# schematic.net
KiCad netlist of a schematic drawn in EAGLE
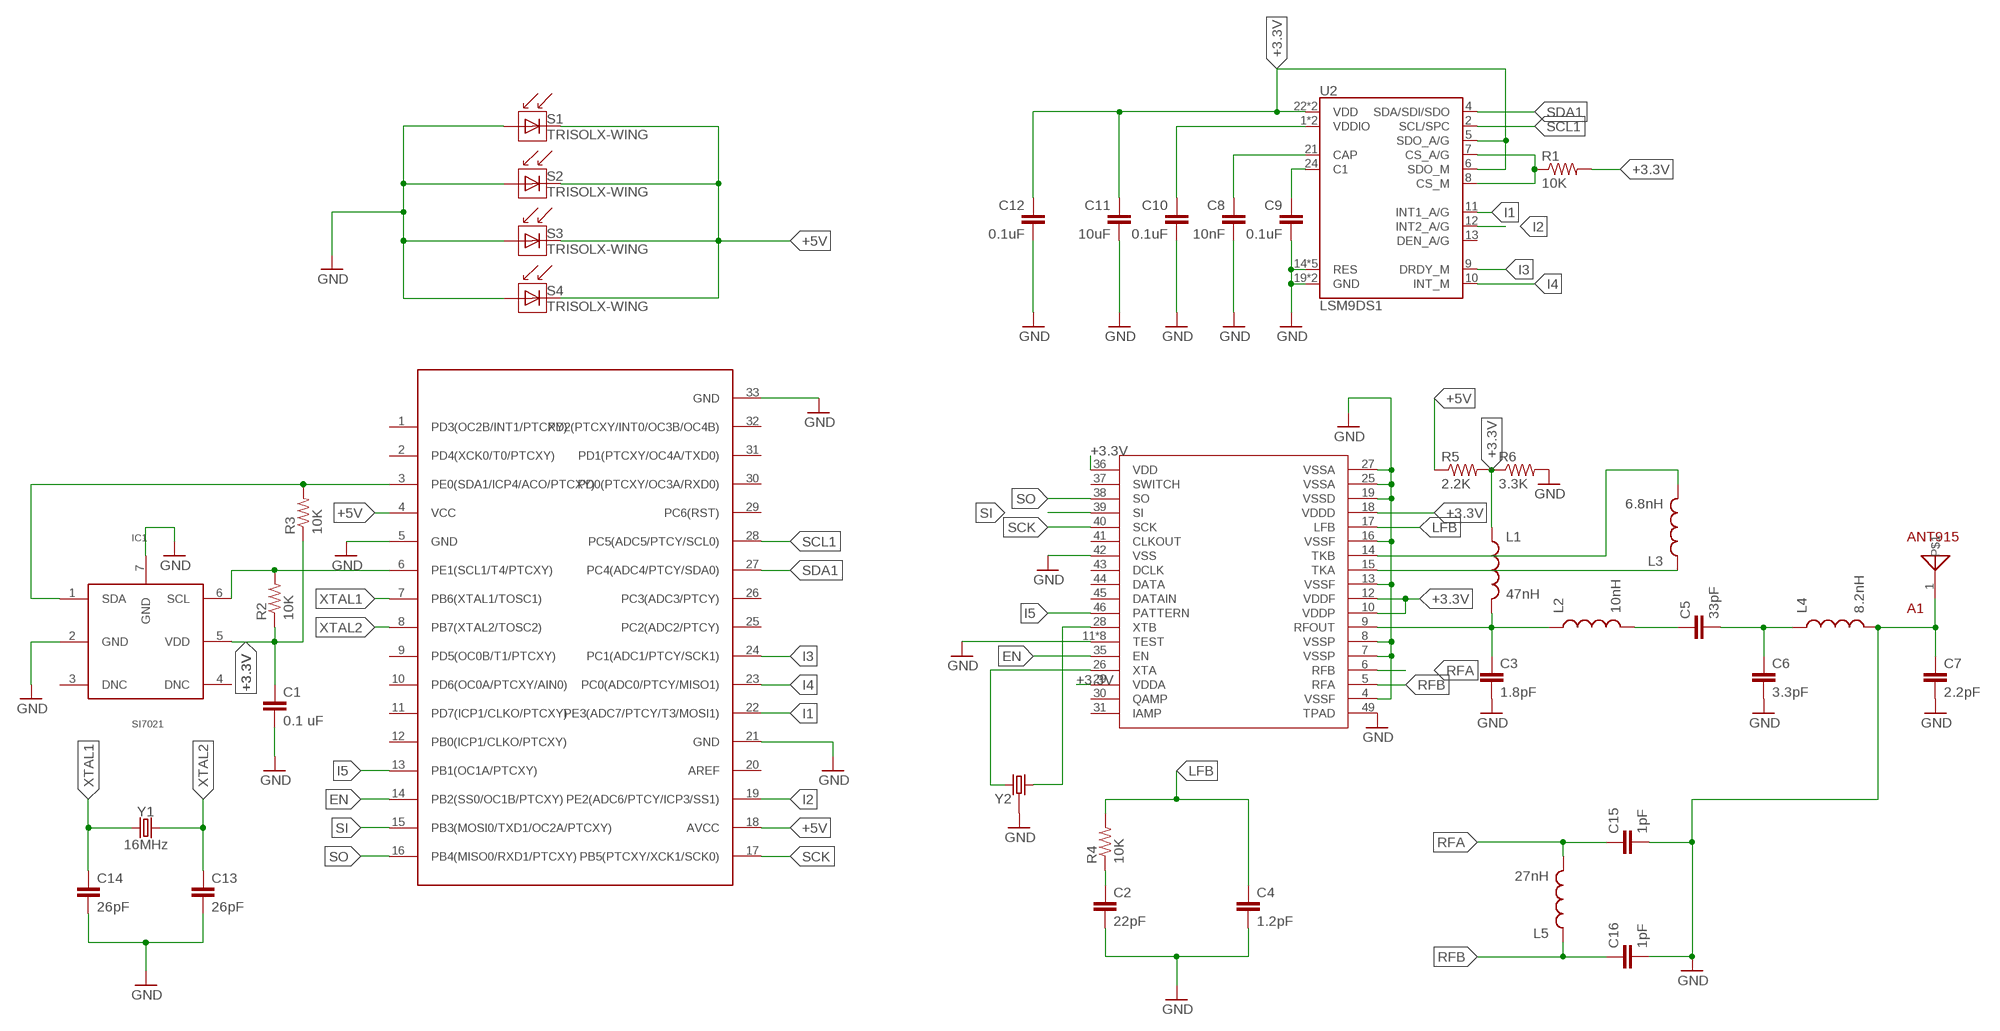
[diagram p0: schematic, sheet 1]

(export (version "E")
  (design (tool "Eeschema 10.0.6"))
  (components
    (comp (ref "A1")
      (value "ANT915")
      (footprint "eagle-import:ANT915")
      (libsource (lib "eagle-import") (part "ANT915"))
    )
    (comp (ref "C1")
      (value "0.1 uF")
      (footprint "eagle-import:0603-CAP")
      (libsource (lib "eagle-import") (part "CAP0603-CAP"))
    )
    (comp (ref "C2")
      (value "22pF")
      (footprint "eagle-import:0603-CAP")
      (libsource (lib "eagle-import") (part "CAP0603-CAP"))
    )
    (comp (ref "C3")
      (value "1.8pF")
      (footprint "eagle-import:0603-CAP")
      (libsource (lib "eagle-import") (part "CAP0603-CAP"))
    )
    (comp (ref "C4")
      (value "1.2pF")
      (footprint "eagle-import:0603-CAP")
      (libsource (lib "eagle-import") (part "CAP0603-CAP"))
    )
    (comp (ref "C5")
      (value "33pF")
      (footprint "eagle-import:0603-CAP")
      (libsource (lib "eagle-import") (part "CAP0603-CAP"))
    )
    (comp (ref "C6")
      (value "3.3pF")
      (footprint "eagle-import:0603-CAP")
      (libsource (lib "eagle-import") (part "CAP0603-CAP"))
    )
    (comp (ref "C7")
      (value "2.2pF")
      (footprint "eagle-import:0603-CAP")
      (libsource (lib "eagle-import") (part "CAP0603-CAP"))
    )
    (comp (ref "C8")
      (value "10nF")
      (footprint "eagle-import:0603-CAP")
      (libsource (lib "eagle-import") (part "CAP0603-CAP"))
    )
    (comp (ref "C9")
      (value "0.1uF")
      (footprint "eagle-import:0603-CAP")
      (libsource (lib "eagle-import") (part "CAP0603-CAP"))
    )
    (comp (ref "C10")
      (value "0.1uF")
      (footprint "eagle-import:0603-CAP")
      (libsource (lib "eagle-import") (part "CAP0603-CAP"))
    )
    (comp (ref "C11")
      (value "10uF")
      (footprint "eagle-import:0603-CAP")
      (libsource (lib "eagle-import") (part "CAP0603-CAP"))
    )
    (comp (ref "C12")
      (value "0.1uF")
      (footprint "eagle-import:0603-CAP")
      (libsource (lib "eagle-import") (part "CAP0603-CAP"))
    )
    (comp (ref "C13")
      (value "26pF")
      (footprint "eagle-import:0603-CAP")
      (libsource (lib "eagle-import") (part "CAP0603-CAP"))
    )
    (comp (ref "C14")
      (value "26pF")
      (footprint "eagle-import:0603-CAP")
      (libsource (lib "eagle-import") (part "CAP0603-CAP"))
    )
    (comp (ref "C15")
      (value "1pF")
      (footprint "eagle-import:0603-CAP")
      (libsource (lib "eagle-import") (part "CAP0603-CAP"))
    )
    (comp (ref "C16")
      (value "1pF")
      (footprint "eagle-import:0603-CAP")
      (libsource (lib "eagle-import") (part "CAP0603-CAP"))
    )
    (comp (ref "IC1")
      (value "SI7021")
      (footprint "eagle-import:SI7021")
      (libsource (lib "eagle-import") (part "SI7021"))
    )
    (comp (ref "IC2")
      (value "ATMEGA328-PB")
      (footprint "eagle-import:ATMEGA328-PB")
      (libsource (lib "eagle-import") (part "ATMEGA328-PB"))
    )
    (comp (ref "IC3")
      (value "XE1203F")
      (footprint "eagle-import:XE1203F")
      (libsource (lib "eagle-import") (part "XE1203F"))
    )
    (comp (ref "L1")
      (value "47nH")
      (footprint "eagle-import:0603")
      (libsource (lib "eagle-import") (part "INDUCTOR0603"))
    )
    (comp (ref "L2")
      (value "10nH")
      (footprint "eagle-import:0603")
      (libsource (lib "eagle-import") (part "INDUCTOR0603"))
    )
    (comp (ref "L3")
      (value "6.8nH")
      (footprint "eagle-import:0603")
      (libsource (lib "eagle-import") (part "INDUCTOR0603"))
    )
    (comp (ref "L4")
      (value "8.2nH")
      (footprint "eagle-import:0603")
      (libsource (lib "eagle-import") (part "INDUCTOR0603"))
    )
    (comp (ref "L5")
      (value "27nH")
      (footprint "eagle-import:0603")
      (libsource (lib "eagle-import") (part "INDUCTOR0603"))
    )
    (comp (ref "R1")
      (value "10K")
      (footprint "eagle-import:0603-RES")
      (libsource (lib "eagle-import") (part "RESISTOR0603-RES"))
    )
    (comp (ref "R2")
      (value "10K")
      (footprint "eagle-import:0603-RES")
      (libsource (lib "eagle-import") (part "RESISTOR0603-RES"))
    )
    (comp (ref "R3")
      (value "10K")
      (footprint "eagle-import:0603-RES")
      (libsource (lib "eagle-import") (part "RESISTOR0603-RES"))
    )
    (comp (ref "R4")
      (value "10K")
      (footprint "eagle-import:0603-RES")
      (libsource (lib "eagle-import") (part "RESISTOR0603-RES"))
    )
    (comp (ref "R5")
      (value "2.2K")
      (footprint "eagle-import:0603-RES")
      (libsource (lib "eagle-import") (part "RESISTOR0603-RES"))
    )
    (comp (ref "R6")
      (value "3.3K")
      (footprint "eagle-import:0603-RES")
      (libsource (lib "eagle-import") (part "RESISTOR0603-RES"))
    )
    (comp (ref "S1")
      (value "TRISOLX-WING")
      (footprint "eagle-import:TRISOLX-T01")
      (libsource (lib "eagle-import") (part "TRISOLX-WING"))
    )
    (comp (ref "S2")
      (value "TRISOLX-WING")
      (footprint "eagle-import:TRISOLX-T01")
      (libsource (lib "eagle-import") (part "TRISOLX-WING"))
    )
    (comp (ref "S3")
      (value "TRISOLX-WING")
      (footprint "eagle-import:TRISOLX-T01")
      (libsource (lib "eagle-import") (part "TRISOLX-WING"))
    )
    (comp (ref "S4")
      (value "TRISOLX-WING")
      (footprint "eagle-import:TRISOLX-T01")
      (libsource (lib "eagle-import") (part "TRISOLX-WING"))
    )
    (comp (ref "U2")
      (value "LSM9DS1")
      (footprint "eagle-import:LGA24-8X4")
      (libsource (lib "eagle-import") (part "LSM9DS1"))
    )
    (comp (ref "Y1")
      (value "16MHz")
      (footprint "eagle-import:CRYSTAL-SMD-2.0X1.6MM")
      (libsource (lib "eagle-import") (part "CRYSTAL-16MHZSMD-2X1.6"))
    )
    (comp (ref "Y2")
      (value "CRYSTAL-26MHZSMD-3.2X2.5")
      (footprint "eagle-import:CRYSTAL-SMD-3.2X2.5MM")
      (libsource (lib "eagle-import") (part "CRYSTAL-26MHZSMD-3.2X2.5"))
    )
  )
  (nets
    (net (code "1") (name "+3.3V") (class "Default")
      (node (ref "C1") (pin "1") (pinfunction "1_1") (pintype "passive"))
      (node (ref "C11") (pin "1") (pinfunction "1_1") (pintype "passive"))
      (node (ref "C12") (pin "1") (pinfunction "1_1") (pintype "passive"))
      (node (ref "IC1") (pin "5") (pinfunction "VDD_5") (pintype "bidirectional"))
      (node (ref "IC3") (pin "10") (pinfunction "VDDP_10") (pintype "bidirectional"))
      (node (ref "IC3") (pin "12") (pinfunction "VDDF_12") (pintype "bidirectional"))
      (node (ref "IC3") (pin "18") (pinfunction "VDDD_18") (pintype "bidirectional"))
      (node (ref "IC3") (pin "29") (pinfunction "VDDA_29") (pintype "bidirectional"))
      (node (ref "IC3") (pin "36") (pinfunction "VDD_36") (pintype "bidirectional"))
      (node (ref "L1") (pin "1") (pinfunction "1_1") (pintype "passive"))
      (node (ref "R1") (pin "2") (pinfunction "2_2") (pintype "passive"))
      (node (ref "R2") (pin "1") (pinfunction "1_1") (pintype "passive"))
      (node (ref "R3") (pin "1") (pinfunction "1_1") (pintype "passive"))
      (node (ref "R5") (pin "2") (pinfunction "2_2") (pintype "passive"))
      (node (ref "R6") (pin "1") (pinfunction "1_1") (pintype "passive"))
      (node (ref "U2") (pin "22") (pinfunction "VDD_22") (pintype "bidirectional"))
      (node (ref "U2") (pin "23") (pinfunction "VDD_23") (pintype "bidirectional"))
      (node (ref "U2") (pin "5") (pinfunction "SDO_A/G_5") (pintype "bidirectional"))
      (node (ref "U2") (pin "6") (pinfunction "SDO_M_6") (pintype "bidirectional"))
    )
    (net (code "2") (name "+5V") (class "Default")
      (node (ref "IC2") (pin "18") (pinfunction "AVCC_18") (pintype "bidirectional"))
      (node (ref "IC2") (pin "4") (pinfunction "VCC_4") (pintype "bidirectional"))
      (node (ref "R5") (pin "1") (pinfunction "1_1") (pintype "passive"))
      (node (ref "S1") (pin "P$2") (pinfunction "C_P$2") (pintype "passive"))
      (node (ref "S2") (pin "P$2") (pinfunction "C_P$2") (pintype "passive"))
      (node (ref "S3") (pin "P$2") (pinfunction "C_P$2") (pintype "passive"))
      (node (ref "S4") (pin "P$2") (pinfunction "C_P$2") (pintype "passive"))
    )
    (net (code "3") (name "EN") (class "Default")
      (node (ref "IC2") (pin "14") (pinfunction "PB2(SS0/OC1B/PTCXY)_14") (pintype "bidirectional"))
      (node (ref "IC3") (pin "35") (pinfunction "EN_35") (pintype "bidirectional"))
    )
    (net (code "4") (name "GND") (class "Default")
      (node (ref "A1") (pin "1") (pinfunction "P$1_1") (pintype "bidirectional"))
      (node (ref "C1") (pin "2") (pinfunction "2_2") (pintype "passive"))
      (node (ref "C10") (pin "2") (pinfunction "2_2") (pintype "passive"))
      (node (ref "C11") (pin "2") (pinfunction "2_2") (pintype "passive"))
      (node (ref "C12") (pin "2") (pinfunction "2_2") (pintype "passive"))
      (node (ref "C13") (pin "2") (pinfunction "2_2") (pintype "passive"))
      (node (ref "C14") (pin "2") (pinfunction "2_2") (pintype "passive"))
      (node (ref "C15") (pin "2") (pinfunction "2_2") (pintype "passive"))
      (node (ref "C16") (pin "2") (pinfunction "2_2") (pintype "passive"))
      (node (ref "C2") (pin "2") (pinfunction "2_2") (pintype "passive"))
      (node (ref "C3") (pin "2") (pinfunction "2_2") (pintype "passive"))
      (node (ref "C4") (pin "2") (pinfunction "2_2") (pintype "passive"))
      (node (ref "C6") (pin "2") (pinfunction "2_2") (pintype "passive"))
      (node (ref "C7") (pin "1") (pinfunction "1_1") (pintype "passive"))
      (node (ref "C7") (pin "2") (pinfunction "2_2") (pintype "passive"))
      (node (ref "C8") (pin "2") (pinfunction "2_2") (pintype "passive"))
      (node (ref "C9") (pin "2") (pinfunction "2_2") (pintype "passive"))
      (node (ref "IC1") (pin "2") (pinfunction "GND_2") (pintype "bidirectional"))
      (node (ref "IC1") (pin "7") (pinfunction "GND_7") (pintype "bidirectional"))
      (node (ref "IC2") (pin "21") (pinfunction "GND_21") (pintype "bidirectional"))
      (node (ref "IC2") (pin "33") (pinfunction "GND_33") (pintype "bidirectional"))
      (node (ref "IC2") (pin "5") (pinfunction "GND_5") (pintype "bidirectional"))
      (node (ref "IC3") (pin "11") (pinfunction "TEST_11") (pintype "bidirectional"))
      (node (ref "IC3") (pin "13") (pinfunction "VSSF_13") (pintype "bidirectional"))
      (node (ref "IC3") (pin "16") (pinfunction "VSSF_16") (pintype "bidirectional"))
      (node (ref "IC3") (pin "19") (pinfunction "VSSD_19") (pintype "bidirectional"))
      (node (ref "IC3") (pin "20") (pinfunction "TEST_20") (pintype "bidirectional"))
      (node (ref "IC3") (pin "21") (pinfunction "TEST_21") (pintype "bidirectional"))
      (node (ref "IC3") (pin "23") (pinfunction "TEST_23") (pintype "bidirectional"))
      (node (ref "IC3") (pin "24") (pinfunction "TEST_24") (pintype "bidirectional"))
      (node (ref "IC3") (pin "25") (pinfunction "VSSA_25") (pintype "bidirectional"))
      (node (ref "IC3") (pin "27") (pinfunction "VSSA_27") (pintype "bidirectional"))
      (node (ref "IC3") (pin "32") (pinfunction "TEST_32") (pintype "bidirectional"))
      (node (ref "IC3") (pin "33") (pinfunction "TEST_33") (pintype "bidirectional"))
      (node (ref "IC3") (pin "34") (pinfunction "TEST_34") (pintype "bidirectional"))
      (node (ref "IC3") (pin "4") (pinfunction "VSSF_4") (pintype "bidirectional"))
      (node (ref "IC3") (pin "42") (pinfunction "VSS_42") (pintype "bidirectional"))
      (node (ref "IC3") (pin "49") (pinfunction "TPAD_49") (pintype "bidirectional"))
      (node (ref "IC3") (pin "7") (pinfunction "VSSP_7") (pintype "bidirectional"))
      (node (ref "IC3") (pin "8") (pinfunction "VSSP_8") (pintype "bidirectional"))
      (node (ref "L4") (pin "2") (pinfunction "2_2") (pintype "passive"))
      (node (ref "R6") (pin "2") (pinfunction "2_2") (pintype "passive"))
      (node (ref "S1") (pin "P$3") (pinfunction "A_P$3") (pintype "passive"))
      (node (ref "S2") (pin "P$3") (pinfunction "A_P$3") (pintype "passive"))
      (node (ref "S3") (pin "P$3") (pinfunction "A_P$3") (pintype "passive"))
      (node (ref "S4") (pin "P$3") (pinfunction "A_P$3") (pintype "passive"))
      (node (ref "U2") (pin "14") (pinfunction "RES_14") (pintype "bidirectional"))
      (node (ref "U2") (pin "15") (pinfunction "RES_15") (pintype "bidirectional"))
      (node (ref "U2") (pin "16") (pinfunction "RES_16") (pintype "bidirectional"))
      (node (ref "U2") (pin "17") (pinfunction "RES_17") (pintype "bidirectional"))
      (node (ref "U2") (pin "18") (pinfunction "RES_18") (pintype "bidirectional"))
      (node (ref "U2") (pin "19") (pinfunction "GND_19") (pintype "bidirectional"))
      (node (ref "U2") (pin "20") (pinfunction "GND_20") (pintype "bidirectional"))
      (node (ref "Y2") (pin "2") (pinfunction "GND_2") (pintype "power_in"))
      (node (ref "Y2") (pin "4") (pinfunction "GND_4") (pintype "power_in"))
    )
    (net (code "5") (name "I1") (class "Default")
      (node (ref "IC2") (pin "22") (pinfunction "PE3(ADC7/PTCY/T3/MOSI1)_22") (pintype "bidirectional"))
      (node (ref "U2") (pin "11") (pinfunction "INT1_A/G_11") (pintype "bidirectional"))
    )
    (net (code "6") (name "I2") (class "Default")
      (node (ref "IC2") (pin "19") (pinfunction "PE2(ADC6/PTCY/ICP3/SS1)_19") (pintype "bidirectional"))
      (node (ref "U2") (pin "12") (pinfunction "INT2_A/G_12") (pintype "bidirectional"))
    )
    (net (code "7") (name "I3") (class "Default")
      (node (ref "IC2") (pin "24") (pinfunction "PC1(ADC1/PTCY/SCK1)_24") (pintype "bidirectional"))
      (node (ref "U2") (pin "9") (pinfunction "DRDY_M_9") (pintype "bidirectional"))
    )
    (net (code "8") (name "I4") (class "Default")
      (node (ref "IC2") (pin "23") (pinfunction "PC0(ADC0/PTCY/MISO1)_23") (pintype "bidirectional"))
      (node (ref "U2") (pin "10") (pinfunction "INT_M_10") (pintype "bidirectional"))
    )
    (net (code "9") (name "I5") (class "Default")
      (node (ref "IC2") (pin "13") (pinfunction "PB1(OC1A/PTCXY)_13") (pintype "bidirectional"))
      (node (ref "IC3") (pin "46") (pinfunction "PATTERN_46") (pintype "bidirectional"))
    )
    (net (code "10") (name "LFB") (class "Default")
      (node (ref "C4") (pin "1") (pinfunction "1_1") (pintype "passive"))
      (node (ref "IC3") (pin "17") (pinfunction "LFB_17") (pintype "bidirectional"))
      (node (ref "R4") (pin "2") (pinfunction "2_2") (pintype "passive"))
    )
    (net (code "11") (name "Net-(C2-Pad1)") (class "Default")
      (node (ref "C2") (pin "1") (pinfunction "1_1") (pintype "passive"))
      (node (ref "R4") (pin "1") (pinfunction "1_1") (pintype "passive"))
    )
    (net (code "12") (name "Net-(C5-Pad1)") (class "Default")
      (node (ref "C5") (pin "1") (pinfunction "1_1") (pintype "passive"))
      (node (ref "L2") (pin "2") (pinfunction "2_2") (pintype "passive"))
    )
    (net (code "13") (name "Net-(C5-Pad2)") (class "Default")
      (node (ref "C5") (pin "2") (pinfunction "2_2") (pintype "passive"))
      (node (ref "C6") (pin "1") (pinfunction "1_1") (pintype "passive"))
      (node (ref "L4") (pin "1") (pinfunction "1_1") (pintype "passive"))
    )
    (net (code "14") (name "Net-(C10-Pad1)") (class "Default")
      (node (ref "C10") (pin "1") (pinfunction "1_1") (pintype "passive"))
      (node (ref "U2") (pin "1") (pinfunction "VDDIO_1") (pintype "bidirectional"))
      (node (ref "U2") (pin "3") (pinfunction "VDDIO_3") (pintype "bidirectional"))
    )
    (net (code "15") (name "Net-(IC1-SCL)") (class "Default")
      (node (ref "IC1") (pin "6") (pinfunction "SCL_6") (pintype "bidirectional"))
      (node (ref "IC2") (pin "6") (pinfunction "PE1(SCL1/T4/PTCXY)_6") (pintype "bidirectional"))
      (node (ref "R2") (pin "2") (pinfunction "2_2") (pintype "passive"))
    )
    (net (code "16") (name "Net-(IC1-SDA)") (class "Default")
      (node (ref "IC1") (pin "1") (pinfunction "SDA_1") (pintype "bidirectional"))
      (node (ref "IC2") (pin "3") (pinfunction "PE0(SDA1/ICP4/ACO/PTCXY)_3") (pintype "bidirectional"))
      (node (ref "R3") (pin "2") (pinfunction "2_2") (pintype "passive"))
    )
    (net (code "17") (name "Net-(IC3-RFOUT)") (class "Default")
      (node (ref "C3") (pin "1") (pinfunction "1_1") (pintype "passive"))
      (node (ref "IC3") (pin "9") (pinfunction "RFOUT_9") (pintype "bidirectional"))
      (node (ref "L1") (pin "2") (pinfunction "2_2") (pintype "passive"))
      (node (ref "L2") (pin "1") (pinfunction "1_1") (pintype "passive"))
    )
    (net (code "18") (name "Net-(IC3-TKA)") (class "Default")
      (node (ref "IC3") (pin "15") (pinfunction "TKA_15") (pintype "bidirectional"))
      (node (ref "L3") (pin "1") (pinfunction "1_1") (pintype "passive"))
    )
    (net (code "19") (name "Net-(IC3-TKB)") (class "Default")
      (node (ref "IC3") (pin "14") (pinfunction "TKB_14") (pintype "bidirectional"))
      (node (ref "L3") (pin "2") (pinfunction "2_2") (pintype "passive"))
    )
    (net (code "20") (name "Net-(IC3-XTA)") (class "Default")
      (node (ref "IC3") (pin "26") (pinfunction "XTA_26") (pintype "bidirectional"))
      (node (ref "Y2") (pin "1") (pinfunction "1_1") (pintype "passive"))
    )
    (net (code "21") (name "Net-(IC3-XTB)") (class "Default")
      (node (ref "IC3") (pin "28") (pinfunction "XTB_28") (pintype "bidirectional"))
      (node (ref "Y2") (pin "3") (pinfunction "2_3") (pintype "passive"))
    )
    (net (code "22") (name "Net-(U2-C1)") (class "Default")
      (node (ref "C9") (pin "1") (pinfunction "1_1") (pintype "passive"))
      (node (ref "U2") (pin "24") (pinfunction "C1_24") (pintype "bidirectional"))
    )
    (net (code "23") (name "Net-(U2-CAP)") (class "Default")
      (node (ref "C8") (pin "1") (pinfunction "1_1") (pintype "passive"))
      (node (ref "U2") (pin "21") (pinfunction "CAP_21") (pintype "bidirectional"))
    )
    (net (code "24") (name "Net-(U2-CS_A{slash}G)") (class "Default")
      (node (ref "R1") (pin "1") (pinfunction "1_1") (pintype "passive"))
      (node (ref "U2") (pin "7") (pinfunction "CS_A/G_7") (pintype "bidirectional"))
      (node (ref "U2") (pin "8") (pinfunction "CS_M_8") (pintype "bidirectional"))
    )
    (net (code "25") (name "RFA") (class "Default")
      (node (ref "C15") (pin "1") (pinfunction "1_1") (pintype "passive"))
      (node (ref "IC3") (pin "6") (pinfunction "RFB_6") (pintype "bidirectional"))
      (node (ref "L5") (pin "2") (pinfunction "2_2") (pintype "passive"))
    )
    (net (code "26") (name "RFB") (class "Default")
      (node (ref "C16") (pin "1") (pinfunction "1_1") (pintype "passive"))
      (node (ref "IC3") (pin "5") (pinfunction "RFA_5") (pintype "bidirectional"))
      (node (ref "L5") (pin "1") (pinfunction "1_1") (pintype "passive"))
    )
    (net (code "27") (name "SCK") (class "Default")
      (node (ref "IC2") (pin "17") (pinfunction "PB5(PTCXY/XCK1/SCK0)_17") (pintype "bidirectional"))
      (node (ref "IC3") (pin "40") (pinfunction "SCK_40") (pintype "bidirectional"))
    )
    (net (code "28") (name "SCL1") (class "Default")
      (node (ref "IC2") (pin "28") (pinfunction "PC5(ADC5/PTCY/SCL0)_28") (pintype "bidirectional"))
      (node (ref "U2") (pin "2") (pinfunction "SCL/SPC_2") (pintype "bidirectional"))
    )
    (net (code "29") (name "SDA1") (class "Default")
      (node (ref "IC2") (pin "27") (pinfunction "PC4(ADC4/PTCY/SDA0)_27") (pintype "bidirectional"))
      (node (ref "U2") (pin "4") (pinfunction "SDA/SDI/SDO_4") (pintype "bidirectional"))
    )
    (net (code "30") (name "SI") (class "Default")
      (node (ref "IC2") (pin "15") (pinfunction "PB3(MOSI0/TXD1/OC2A/PTCXY)_15") (pintype "bidirectional"))
      (node (ref "IC3") (pin "39") (pinfunction "SI_39") (pintype "bidirectional"))
    )
    (net (code "31") (name "SO") (class "Default")
      (node (ref "IC2") (pin "16") (pinfunction "PB4(MISO0/RXD1/PTCXY)_16") (pintype "bidirectional"))
      (node (ref "IC3") (pin "38") (pinfunction "SO_38") (pintype "bidirectional"))
    )
    (net (code "32") (name "XTAL1") (class "Default")
      (node (ref "C14") (pin "1") (pinfunction "1_1") (pintype "passive"))
      (node (ref "IC2") (pin "7") (pinfunction "PB6(XTAL1/TOSC1)_7") (pintype "bidirectional"))
      (node (ref "Y1") (pin "1") (pinfunction "1_1") (pintype "passive"))
    )
    (net (code "33") (name "XTAL2") (class "Default")
      (node (ref "C13") (pin "1") (pinfunction "1_1") (pintype "passive"))
      (node (ref "IC2") (pin "8") (pinfunction "PB7(XTAL2/TOSC2)_8") (pintype "bidirectional"))
      (node (ref "Y1") (pin "3") (pinfunction "2_3") (pintype "passive"))
    )
    (net (code "34") (name "unconnected-(IC1-DNC-Pad3)") (class "Default")
      (node (ref "IC1") (pin "3") (pinfunction "DNC_3") (pintype "bidirectional"))
    )
    (net (code "35") (name "unconnected-(IC1-DNC-Pad4)") (class "Default")
      (node (ref "IC1") (pin "4") (pinfunction "DNC_4") (pintype "bidirectional"))
    )
    (net (code "36") (name "unconnected-(IC2-AREF-Pad20)") (class "Default")
      (node (ref "IC2") (pin "20") (pinfunction "AREF_20") (pintype "bidirectional"))
    )
    (net (code "37") (name "unconnected-(IC2-PB0(ICP1{slash}CLKO{slash}PTCXY)-Pad12)") (class "Default")
      (node (ref "IC2") (pin "12") (pinfunction "PB0(ICP1/CLKO/PTCXY)_12") (pintype "bidirectional"))
    )
    (net (code "38") (name "unconnected-(IC2-PC2(ADC2{slash}PTCY)-Pad25)") (class "Default")
      (node (ref "IC2") (pin "25") (pinfunction "PC2(ADC2/PTCY)_25") (pintype "bidirectional"))
    )
    (net (code "39") (name "unconnected-(IC2-PC3(ADC3{slash}PTCY)-Pad26)") (class "Default")
      (node (ref "IC2") (pin "26") (pinfunction "PC3(ADC3/PTCY)_26") (pintype "bidirectional"))
    )
    (net (code "40") (name "unconnected-(IC2-PC6(RST)-Pad29)") (class "Default")
      (node (ref "IC2") (pin "29") (pinfunction "PC6(RST)_29") (pintype "bidirectional"))
    )
    (net (code "41") (name "unconnected-(IC2-PD0(PTCXY{slash}OC3A{slash}RXD0)-Pad30)") (class "Default")
      (node (ref "IC2") (pin "30") (pinfunction "PD0(PTCXY/OC3A/RXD0)_30") (pintype "bidirectional"))
    )
    (net (code "42") (name "unconnected-(IC2-PD1(PTCXY{slash}OC4A{slash}TXD0)-Pad31)") (class "Default")
      (node (ref "IC2") (pin "31") (pinfunction "PD1(PTCXY/OC4A/TXD0)_31") (pintype "bidirectional"))
    )
    (net (code "43") (name "unconnected-(IC2-PD2(PTCXY{slash}INT0{slash}OC3B{slash}OC4B)-Pad32)") (class "Default")
      (node (ref "IC2") (pin "32") (pinfunction "PD2(PTCXY/INT0/OC3B/OC4B)_32") (pintype "bidirectional"))
    )
    (net (code "44") (name "unconnected-(IC2-PD3(OC2B{slash}INT1{slash}PTCXY)-Pad1)") (class "Default")
      (node (ref "IC2") (pin "1") (pinfunction "PD3(OC2B/INT1/PTCXY)_1") (pintype "bidirectional"))
    )
    (net (code "45") (name "unconnected-(IC2-PD4(XCK0{slash}T0{slash}PTCXY)-Pad2)") (class "Default")
      (node (ref "IC2") (pin "2") (pinfunction "PD4(XCK0/T0/PTCXY)_2") (pintype "bidirectional"))
    )
    (net (code "46") (name "unconnected-(IC2-PD5(OC0B{slash}T1{slash}PTCXY)-Pad9)") (class "Default")
      (node (ref "IC2") (pin "9") (pinfunction "PD5(OC0B/T1/PTCXY)_9") (pintype "bidirectional"))
    )
    (net (code "47") (name "unconnected-(IC2-PD6(OC0A{slash}PTCXY{slash}AIN0)-Pad10)") (class "Default")
      (node (ref "IC2") (pin "10") (pinfunction "PD6(OC0A/PTCXY/AIN0)_10") (pintype "bidirectional"))
    )
    (net (code "48") (name "unconnected-(IC2-PD7(ICP1{slash}CLKO{slash}PTCXY)-Pad11)") (class "Default")
      (node (ref "IC2") (pin "11") (pinfunction "PD7(ICP1/CLKO/PTCXY)_11") (pintype "bidirectional"))
    )
    (net (code "49") (name "unconnected-(IC3-CLKOUT-Pad41)") (class "Default")
      (node (ref "IC3") (pin "41") (pinfunction "CLKOUT_41") (pintype "bidirectional"))
    )
    (net (code "50") (name "unconnected-(IC3-DATA-Pad44)") (class "Default")
      (node (ref "IC3") (pin "44") (pinfunction "DATA_44") (pintype "bidirectional"))
    )
    (net (code "51") (name "unconnected-(IC3-DATAIN-Pad45)") (class "Default")
      (node (ref "IC3") (pin "45") (pinfunction "DATAIN_45") (pintype "bidirectional"))
    )
    (net (code "52") (name "unconnected-(IC3-DCLK-Pad43)") (class "Default")
      (node (ref "IC3") (pin "43") (pinfunction "DCLK_43") (pintype "bidirectional"))
    )
    (net (code "53") (name "unconnected-(IC3-IAMP-Pad31)") (class "Default")
      (node (ref "IC3") (pin "31") (pinfunction "IAMP_31") (pintype "bidirectional"))
    )
    (net (code "54") (name "unconnected-(IC3-QAMP-Pad30)") (class "Default")
      (node (ref "IC3") (pin "30") (pinfunction "QAMP_30") (pintype "bidirectional"))
    )
    (net (code "55") (name "unconnected-(IC3-SWITCH-Pad37)") (class "Default")
      (node (ref "IC3") (pin "37") (pinfunction "SWITCH_37") (pintype "bidirectional"))
    )
    (net (code "56") (name "unconnected-(U2-DEN_A{slash}G-Pad13)") (class "Default")
      (node (ref "U2") (pin "13") (pinfunction "DEN_A/G_13") (pintype "bidirectional"))
    )
  )
)
